# 09-USBUart_PPSMUX_UARTMUX.net
KiCad netlist of a schematic drawn in Altium Designer
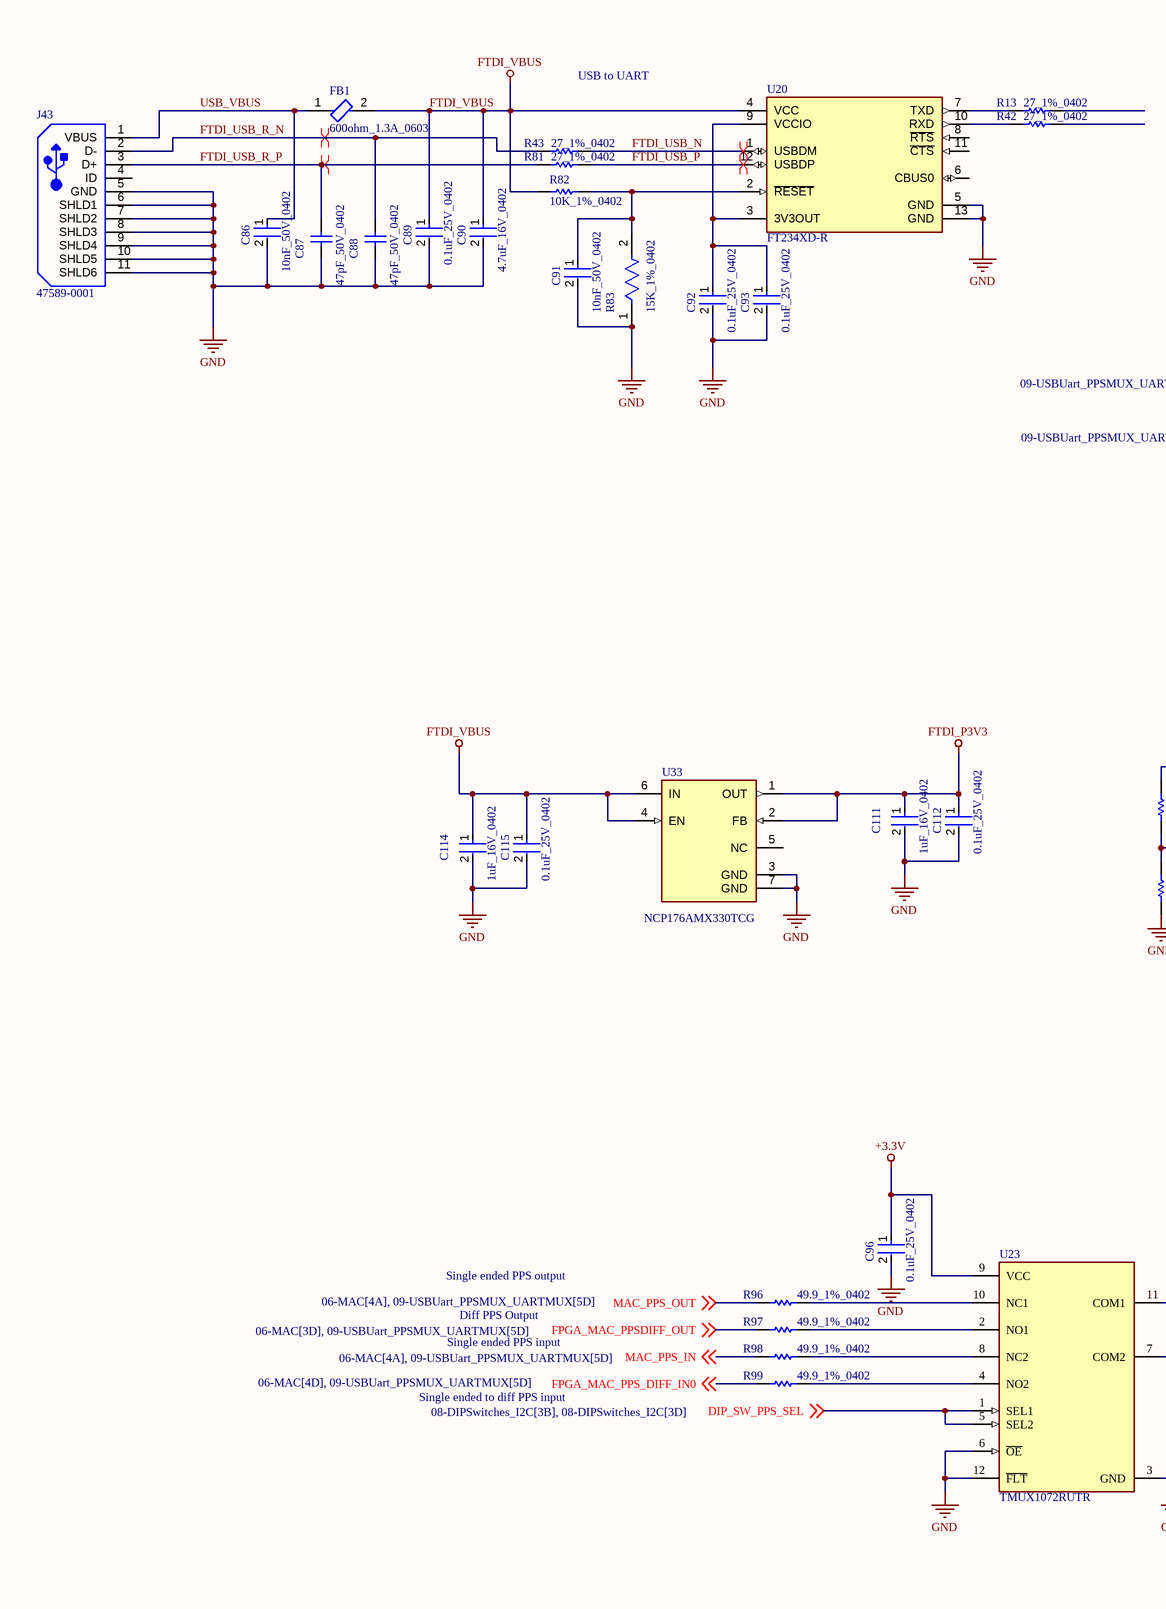
[diagram p0: 09-USBUart_PPSMUX_UARTMUX.SchDoc, left]
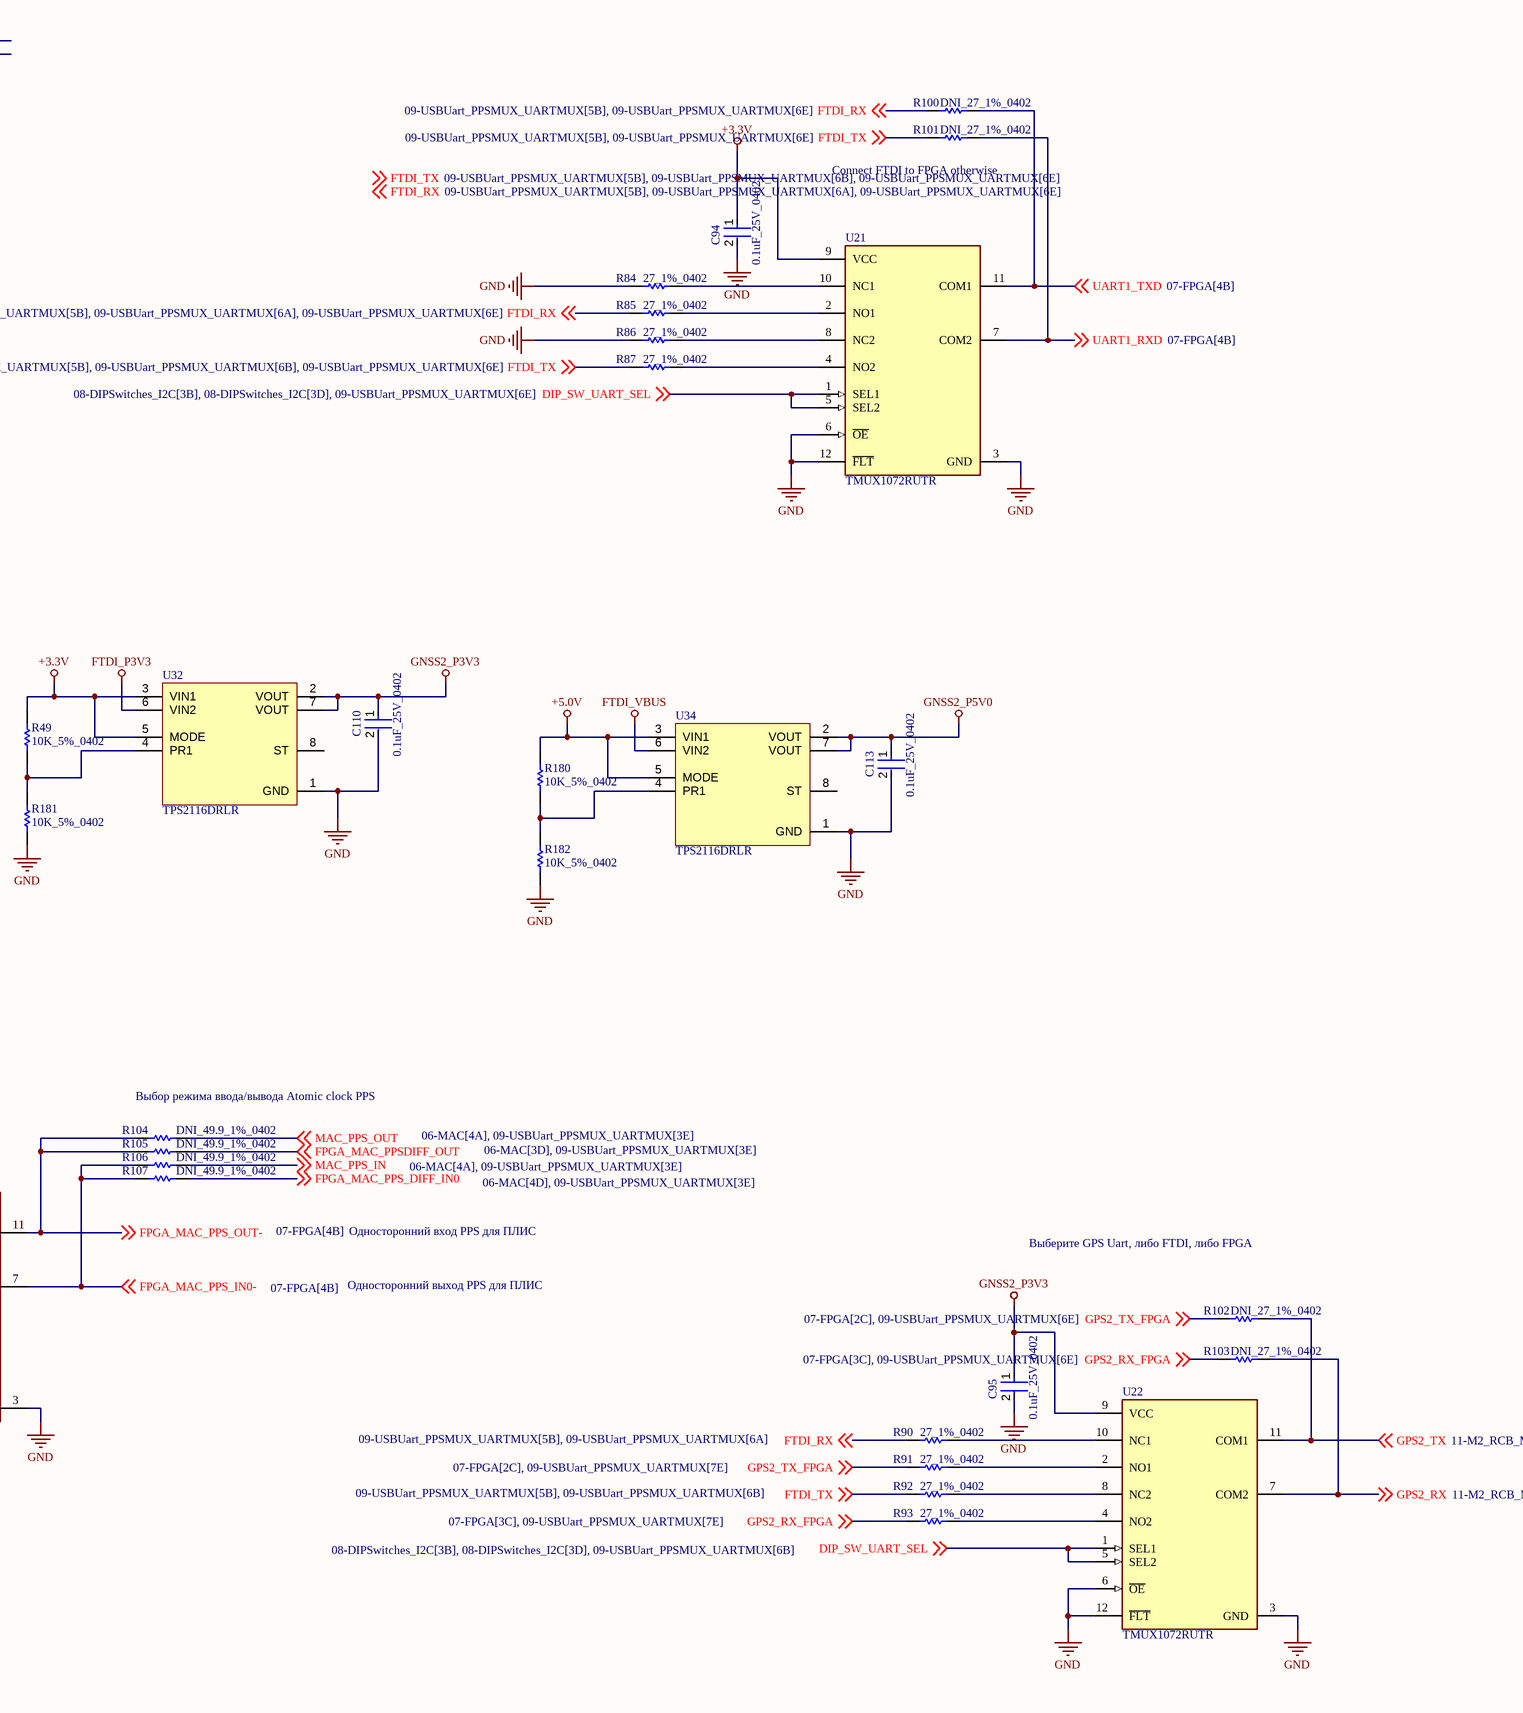
[diagram p1: 09-USBUart_PPSMUX_UARTMUX.SchDoc, right]

(export (version "E")
  (design (tool "Eeschema 10.0.6"))
  (components
    (comp (ref "C86")
      (value "10nF_50V_0402")
      (footprint "FP-CC0402-MFG")
      (description "CAP CER 10000PF 50V X7R 0402")
      (fields
        (field (name "OCTOPART") "https://octopart.com/cc0402krx7r9bb103-yageo-8376513")
        (field (name "MANUFACTURER PART NUMBER") "CC0402KRX7R9BB103")
      )
      (libsource (lib "Altium Content Vault") (part "11868f565c42a9108669ba33697ecf6"))
    )
    (comp (ref "C87")
      (value "47pF_50V_0402")
      (footprint "CAPC1005X55X25LL05T10")
      (fields (field (name "PART NUMBER") "GRM1555C1H470JA01D") (field (name "MANUFACTURER") "Murata"))
      (libsource (lib "Altium Content Vault") (part "CAP"))
    )
    (comp (ref "C88")
      (value "47pF_50V_0402")
      (footprint "CAPC1005X55X25LL05T10")
      (fields (field (name "PART NUMBER") "GRM1555C1H470JA01D") (field (name "MANUFACTURER") "Murata"))
      (libsource (lib "Altium Content Vault") (part "CAP"))
    )
    (comp (ref "C89")
      (value "0.1uF_25V_0402")
      (footprint "FP-0402-L_1_0_1-W_0_5_0_1-IPC_C")
      (description "General Purpose Ceramic Capacitor, 0402, 100nF, 10%, X7R, 15%, 25V")
      (fields (field (name "VOLTAGE") "25V") (field (name "TOLERANCE") "10%"))
      (libsource (lib "Altium Content Vault") (part "b4654b650e69147ec39a6b967a45e02"))
    )
    (comp (ref "C90")
      (value "4.7uF_16V_0402")
      (footprint "FP-CL829-IPC_C")
      (description "Cap Ceramic 4.7uF 16V X5R ±20% SMD 0402 +85°C Paper T/R")
      (fields (field (name "TOLERANCE") "20%"))
      (libsource (lib "Altium Content Vault") (part "b4654b650e69147ec39a6b967a45e02"))
    )
    (comp (ref "C91")
      (value "10nF_50V_0402")
      (footprint "FP-CC0402-MFG")
      (description "CAP CER 10000PF 50V X7R 0402")
      (fields
        (field (name "OCTOPART") "https://octopart.com/cc0402krx7r9bb103-yageo-8376513")
        (field (name "MANUFACTURER PART NUMBER") "CC0402KRX7R9BB103")
      )
      (libsource (lib "Altium Content Vault") (part "11868f565c42a9108669ba33697ecf6"))
    )
    (comp (ref "C92")
      (value "0.1uF_25V_0402")
      (footprint "FP-0402-L_1_0_1-W_0_5_0_1-IPC_C")
      (description "General Purpose Ceramic Capacitor, 0402, 100nF, 10%, X7R, 15%, 25V")
      (fields (field (name "VOLTAGE") "25V") (field (name "TOLERANCE") "10%"))
      (libsource (lib "Altium Content Vault") (part "b4654b650e69147ec39a6b967a45e02"))
    )
    (comp (ref "C93")
      (value "0.1uF_25V_0402")
      (footprint "FP-0402-L_1_0_1-W_0_5_0_1-IPC_C")
      (description "General Purpose Ceramic Capacitor, 0402, 100nF, 10%, X7R, 15%, 25V")
      (fields (field (name "VOLTAGE") "25V") (field (name "TOLERANCE") "10%"))
      (libsource (lib "Altium Content Vault") (part "b4654b650e69147ec39a6b967a45e02"))
    )
    (comp (ref "C94")
      (value "0.1uF_25V_0402")
      (footprint "FP-0402-L_1_0_1-W_0_5_0_1-IPC_C")
      (description "General Purpose Ceramic Capacitor, 0402, 100nF, 10%, X7R, 15%, 25V")
      (fields (field (name "VOLTAGE") "25V") (field (name "TOLERANCE") "10%"))
      (libsource (lib "Altium Content Vault") (part "b4654b650e69147ec39a6b967a45e02"))
    )
    (comp (ref "C95")
      (value "0.1uF_25V_0402")
      (footprint "FP-0402-L_1_0_1-W_0_5_0_1-IPC_C")
      (description "General Purpose Ceramic Capacitor, 0402, 100nF, 10%, X7R, 15%, 25V")
      (fields (field (name "VOLTAGE") "25V") (field (name "TOLERANCE") "10%"))
      (libsource (lib "Altium Content Vault") (part "b4654b650e69147ec39a6b967a45e02"))
    )
    (comp (ref "C96")
      (value "0.1uF_25V_0402")
      (footprint "FP-0402-L_1_0_1-W_0_5_0_1-IPC_C")
      (description "General Purpose Ceramic Capacitor, 0402, 100nF, 10%, X7R, 15%, 25V")
      (fields (field (name "VOLTAGE") "25V") (field (name "TOLERANCE") "10%"))
      (libsource (lib "Altium Content Vault") (part "b4654b650e69147ec39a6b967a45e02"))
    )
    (comp (ref "C110")
      (value "0.1uF_25V_0402")
      (footprint "FP-0402-L_1_0_1-W_0_5_0_1-IPC_C")
      (description "General Purpose Ceramic Capacitor, 0402, 100nF, 10%, X7R, 15%, 25V")
      (fields (field (name "VOLTAGE") "25V") (field (name "TOLERANCE") "10%"))
      (libsource (lib "Altium Content Vault") (part "b4654b650e69147ec39a6b967a45e02"))
    )
    (comp (ref "C111")
      (value "1uF_16V_0402")
      (footprint "FP-0402-L_1_0_0_05-W_0_5-IPC_A")
      (description "None")
      (fields (field (name "TOLERANCE") "10%"))
      (libsource (lib "Altium Content Vault") (part "b4654b650e69147ec39a6b967a45e02"))
    )
    (comp (ref "C112")
      (value "0.1uF_25V_0402")
      (footprint "FP-0402-L_1_0_1-W_0_5_0_1-IPC_C")
      (description "General Purpose Ceramic Capacitor, 0402, 100nF, 10%, X7R, 15%, 25V")
      (fields (field (name "VOLTAGE") "25V") (field (name "TOLERANCE") "10%"))
      (libsource (lib "Altium Content Vault") (part "b4654b650e69147ec39a6b967a45e02"))
    )
    (comp (ref "C113")
      (value "0.1uF_25V_0402")
      (footprint "FP-0402-L_1_0_1-W_0_5_0_1-IPC_C")
      (description "General Purpose Ceramic Capacitor, 0402, 100nF, 10%, X7R, 15%, 25V")
      (fields (field (name "VOLTAGE") "25V") (field (name "TOLERANCE") "10%"))
      (libsource (lib "Altium Content Vault") (part "b4654b650e69147ec39a6b967a45e02"))
    )
    (comp (ref "C114")
      (value "1uF_16V_0402")
      (footprint "FP-0402-L_1_0_0_05-W_0_5-IPC_A")
      (description "None")
      (fields (field (name "TOLERANCE") "10%"))
      (libsource (lib "Altium Content Vault") (part "b4654b650e69147ec39a6b967a45e02"))
    )
    (comp (ref "C115")
      (value "0.1uF_25V_0402")
      (footprint "FP-0402-L_1_0_1-W_0_5_0_1-IPC_C")
      (description "General Purpose Ceramic Capacitor, 0402, 100nF, 10%, X7R, 15%, 25V")
      (fields (field (name "VOLTAGE") "25V") (field (name "TOLERANCE") "10%"))
      (libsource (lib "Altium Content Vault") (part "b4654b650e69147ec39a6b967a45e02"))
    )
    (comp (ref "FB1")
      (value "600ohm_1.3A_0603")
      (footprint "FP-BLM18-0_15-t0_8-IPC_A")
      (description "Chip Ferrite Bead, 0603, 600Ω @ 100MHz, 0.15Ω, 25%, 1.3A")
      (fields (field (name "TOLERANCE") "25%"))
      (libsource (lib "Altium Content Vault") (part "5f30dd21d616792df468990f7003faa"))
    )
    (comp (ref "J43")
      (value "47589-0001")
      (footprint "MOLX-47589-0001_V")
      (description "Right Angle Female Type AB Micro USB Connector, 30 V, 1.8 A, -30 to 85 degC, RoHS, Tape and Reel")
      (fields (field (name "MANUFACTURER") "Molex"))
      (libsource (lib "Altium Content Vault") (part "USB-5-6SHLD"))
    )
    (comp (ref "R13")
      (value "27_1%_0402")
      (footprint "RESC1005X40X25NL05T05")
      (fields (field (name "PART NUMBER") "CRCW040227R0FKED") (field (name "MANUFACTURER") "Vishay Dale"))
      (libsource (lib "Altium Content Vault") (part "RES"))
    )
    (comp (ref "R42")
      (value "27_1%_0402")
      (footprint "RESC1005X40X25NL05T05")
      (fields (field (name "PART NUMBER") "CRCW040227R0FKED") (field (name "MANUFACTURER") "Vishay Dale"))
      (libsource (lib "Altium Content Vault") (part "RES"))
    )
    (comp (ref "R43")
      (value "27_1%_0402")
      (footprint "RESC1005X40X25NL05T05")
      (fields (field (name "PART NUMBER") "CRCW040227R0FKED") (field (name "MANUFACTURER") "Vishay Dale"))
      (libsource (lib "Altium Content Vault") (part "RES"))
    )
    (comp (ref "R49")
      (value "10K_5%_0402")
      (footprint "RESC1005X40X25ML05T05")
      (fields (field (name "PART NUMBER") "ERJ-2GEJ103X") (field (name "MANUFACTURER") "Panasonic"))
      (libsource (lib "Altium Content Vault") (part "RES"))
    )
    (comp (ref "R81")
      (value "27_1%_0402")
      (footprint "RESC1005X40X25NL05T05")
      (fields (field (name "PART NUMBER") "CRCW040227R0FKED") (field (name "MANUFACTURER") "Vishay Dale"))
      (libsource (lib "Altium Content Vault") (part "RES"))
    )
    (comp (ref "R82")
      (value "10K_1%_0402")
      (footprint "RESC1005X40X25LL05T10")
      (fields (field (name "PART NUMBER") "RC0402FR-0710KL") (field (name "MANUFACTURER") "Yageo / Phycomp"))
      (libsource (lib "Altium Content Vault") (part "RES"))
    )
    (comp (ref "R83")
      (value "15K_1%_0402")
      (footprint "FP-ERJ2R-MFG")
      (description "RES SMD 15K OHM 1% 1/10W 0402")
      (fields (field (name "TOLERANCE") "1%") (field (name "MANUFACTURER PART NUMBER") "ERJ-2RKF1502X"))
      (libsource (lib "Altium Content Vault") (part "1029c3af85768c4190bb7ad29bc67b5"))
    )
    (comp (ref "R84")
      (value "27_1%_0402")
      (footprint "RESC1005X40X25NL05T05")
      (fields (field (name "PART NUMBER") "CRCW040227R0FKED") (field (name "MANUFACTURER") "Vishay Dale"))
      (libsource (lib "Altium Content Vault") (part "RES"))
    )
    (comp (ref "R85")
      (value "27_1%_0402")
      (footprint "RESC1005X40X25NL05T05")
      (fields (field (name "PART NUMBER") "CRCW040227R0FKED") (field (name "MANUFACTURER") "Vishay Dale"))
      (libsource (lib "Altium Content Vault") (part "RES"))
    )
    (comp (ref "R86")
      (value "27_1%_0402")
      (footprint "RESC1005X40X25NL05T05")
      (fields (field (name "PART NUMBER") "CRCW040227R0FKED") (field (name "MANUFACTURER") "Vishay Dale"))
      (libsource (lib "Altium Content Vault") (part "RES"))
    )
    (comp (ref "R87")
      (value "27_1%_0402")
      (footprint "RESC1005X40X25NL05T05")
      (fields (field (name "PART NUMBER") "CRCW040227R0FKED") (field (name "MANUFACTURER") "Vishay Dale"))
      (libsource (lib "Altium Content Vault") (part "RES"))
    )
    (comp (ref "R90")
      (value "27_1%_0402")
      (footprint "RESC1005X40X25NL05T05")
      (fields (field (name "PART NUMBER") "CRCW040227R0FKED") (field (name "MANUFACTURER") "Vishay Dale"))
      (libsource (lib "Altium Content Vault") (part "RES"))
    )
    (comp (ref "R91")
      (value "27_1%_0402")
      (footprint "RESC1005X40X25NL05T05")
      (fields (field (name "PART NUMBER") "CRCW040227R0FKED") (field (name "MANUFACTURER") "Vishay Dale"))
      (libsource (lib "Altium Content Vault") (part "RES"))
    )
    (comp (ref "R92")
      (value "27_1%_0402")
      (footprint "RESC1005X40X25NL05T05")
      (fields (field (name "PART NUMBER") "CRCW040227R0FKED") (field (name "MANUFACTURER") "Vishay Dale"))
      (libsource (lib "Altium Content Vault") (part "RES"))
    )
    (comp (ref "R93")
      (value "27_1%_0402")
      (footprint "RESC1005X40X25NL05T05")
      (fields (field (name "PART NUMBER") "CRCW040227R0FKED") (field (name "MANUFACTURER") "Vishay Dale"))
      (libsource (lib "Altium Content Vault") (part "RES"))
    )
    (comp (ref "R96")
      (value "49.9_1%_0402")
      (footprint "RESC1005X40X25LL05T10")
      (fields (field (name "MANUFACTURER") "Yageo / Phycomp") (field (name "PART NUMBER") "RC0402FR-0749R9L"))
      (libsource (lib "Altium Content Vault") (part "RES"))
    )
    (comp (ref "R97")
      (value "49.9_1%_0402")
      (footprint "RESC1005X40X25LL05T10")
      (fields (field (name "MANUFACTURER") "Yageo / Phycomp") (field (name "PART NUMBER") "RC0402FR-0749R9L"))
      (libsource (lib "Altium Content Vault") (part "RES"))
    )
    (comp (ref "R98")
      (value "49.9_1%_0402")
      (footprint "RESC1005X40X25LL05T10")
      (fields (field (name "MANUFACTURER") "Yageo / Phycomp") (field (name "PART NUMBER") "RC0402FR-0749R9L"))
      (libsource (lib "Altium Content Vault") (part "RES"))
    )
    (comp (ref "R99")
      (value "49.9_1%_0402")
      (footprint "RESC1005X40X25LL05T10")
      (fields (field (name "MANUFACTURER") "Yageo / Phycomp") (field (name "PART NUMBER") "RC0402FR-0749R9L"))
      (libsource (lib "Altium Content Vault") (part "RES"))
    )
    (comp (ref "R100")
      (value "DNI_27_1%_0402")
      (footprint "RESC1005X40X25NL05T05")
      (fields (field (name "PART NUMBER") "CRCW040227R0FKED") (field (name "MANUFACTURER") "Vishay Dale"))
      (libsource (lib "Altium Content Vault") (part "RES"))
    )
    (comp (ref "R101")
      (value "DNI_27_1%_0402")
      (footprint "RESC1005X40X25NL05T05")
      (fields (field (name "PART NUMBER") "CRCW040227R0FKED") (field (name "MANUFACTURER") "Vishay Dale"))
      (libsource (lib "Altium Content Vault") (part "RES"))
    )
    (comp (ref "R102")
      (value "DNI_27_1%_0402")
      (footprint "RESC1005X40X25NL05T05")
      (fields (field (name "PART NUMBER") "CRCW040227R0FKED") (field (name "MANUFACTURER") "Vishay Dale"))
      (libsource (lib "Altium Content Vault") (part "RES"))
    )
    (comp (ref "R103")
      (value "DNI_27_1%_0402")
      (footprint "RESC1005X40X25NL05T05")
      (fields (field (name "PART NUMBER") "CRCW040227R0FKED") (field (name "MANUFACTURER") "Vishay Dale"))
      (libsource (lib "Altium Content Vault") (part "RES"))
    )
    (comp (ref "R104")
      (value "DNI_49.9_1%_0402")
      (footprint "RESC1005X40X25LL05T10")
      (fields (field (name "MANUFACTURER") "Yageo / Phycomp") (field (name "PART NUMBER") "RC0402FR-0749R9L"))
      (libsource (lib "Altium Content Vault") (part "RES"))
    )
    (comp (ref "R105")
      (value "DNI_49.9_1%_0402")
      (footprint "RESC1005X40X25LL05T10")
      (fields (field (name "MANUFACTURER") "Yageo / Phycomp") (field (name "PART NUMBER") "RC0402FR-0749R9L"))
      (libsource (lib "Altium Content Vault") (part "RES"))
    )
    (comp (ref "R106")
      (value "DNI_49.9_1%_0402")
      (footprint "RESC1005X40X25LL05T10")
      (fields (field (name "MANUFACTURER") "Yageo / Phycomp") (field (name "PART NUMBER") "RC0402FR-0749R9L"))
      (libsource (lib "Altium Content Vault") (part "RES"))
    )
    (comp (ref "R107")
      (value "DNI_49.9_1%_0402")
      (footprint "RESC1005X40X25LL05T10")
      (fields (field (name "MANUFACTURER") "Yageo / Phycomp") (field (name "PART NUMBER") "RC0402FR-0749R9L"))
      (libsource (lib "Altium Content Vault") (part "RES"))
    )
    (comp (ref "R180")
      (value "10K_5%_0402")
      (footprint "RESC1005X40X25ML05T05")
      (fields (field (name "PART NUMBER") "ERJ-2GEJ103X") (field (name "MANUFACTURER") "Panasonic"))
      (libsource (lib "Altium Content Vault") (part "RES"))
    )
    (comp (ref "R181")
      (value "10K_5%_0402")
      (footprint "RESC1005X40X25ML05T05")
      (fields (field (name "PART NUMBER") "ERJ-2GEJ103X") (field (name "MANUFACTURER") "Panasonic"))
      (libsource (lib "Altium Content Vault") (part "RES"))
    )
    (comp (ref "R182")
      (value "10K_5%_0402")
      (footprint "RESC1005X40X25ML05T05")
      (fields (field (name "PART NUMBER") "ERJ-2GEJ103X") (field (name "MANUFACTURER") "Panasonic"))
      (libsource (lib "Altium Content Vault") (part "RES"))
    )
    (comp (ref "U20")
      (value "FT234XD-R")
      (footprint "FP-DFN-12-IPC_B")
      (description "IC USB SERIAL BASIC UART 12DFN")
      (libsource (lib "Altium Content Vault") (part "4bef3367ed9f9051bcb84ab46edda1c"))
    )
    (comp (ref "U21")
      (value "TMUX1072RUTR")
      (footprint "FP-RUT0012A-MFG")
      (description "IC SWITCH SPDT DUAL 12UQFN")
      (libsource (lib "Altium Content Vault") (part "12a319ab100cd6cfe745e35972674f5"))
    )
    (comp (ref "U22")
      (value "TMUX1072RUTR")
      (footprint "FP-RUT0012A-MFG")
      (description "IC SWITCH SPDT DUAL 12UQFN")
      (libsource (lib "Altium Content Vault") (part "12a319ab100cd6cfe745e35972674f5"))
    )
    (comp (ref "U23")
      (value "TMUX1072RUTR")
      (footprint "FP-RUT0012A-MFG")
      (description "IC SWITCH SPDT DUAL 12UQFN")
      (libsource (lib "Altium Content Vault") (part "12a319ab100cd6cfe745e35972674f5"))
    )
    (comp (ref "U32")
      (value "TPS2116DRLR")
      (footprint "IC_TPS2116")
      (description "1.6-V to 5.5-V, 40-mΩ, 2.5-A, low-IQ, priority power multiplexer 8-SOT-5X3 -40 to 125")
      (fields (field (name "MF") "Texas Instruments"))
      (libsource (lib "LotusSound") (part "IC_TPS2116DRLR"))
    )
    (comp (ref "U33")
      (value "NCP176AMX330TCG")
      (footprint "FP-711AT-MFG")
      (description "IC REG LINEAR 3.3V 500MA 6XDFN")
      (fields
        (field (name "MANUFACTURER") "ON Semiconductor")
        (field (name "OCTOPART") "https://octopart.com/ncp176amx330tcg-on+semiconductor-61522616")
      )
      (libsource (lib "Altium Content Vault") (part "a38d0f79c2a9f01c07a7e52882ed186"))
    )
    (comp (ref "U34")
      (value "TPS2116DRLR")
      (footprint "IC_TPS2116")
      (description "1.6-V to 5.5-V, 40-mΩ, 2.5-A, low-IQ, priority power multiplexer 8-SOT-5X3 -40 to 125")
      (fields (field (name "MF") "Texas Instruments"))
      (libsource (lib "LotusSound") (part "IC_TPS2116DRLR"))
    )
  )
  (nets
    (net (code "1") (name "+3.3V") (class "Default")
      (node (ref "C94") (pin "1") (pinfunction "1_1") (pintype "passive"))
      (node (ref "C96") (pin "1") (pinfunction "1_1") (pintype "passive"))
      (node (ref "R49") (pin "2") (pinfunction "2_2") (pintype "passive"))
      (node (ref "U21") (pin "9") (pinfunction "VCC_9") (pintype "power_in"))
      (node (ref "U23") (pin "9") (pinfunction "VCC_9") (pintype "power_in"))
      (node (ref "U32") (pin "3") (pinfunction "VIN1_3") (pintype "passive"))
      (node (ref "U32") (pin "5") (pinfunction "MODE_5") (pintype "passive"))
    )
    (net (code "2") (name "+5.0V") (class "Default")
      (node (ref "R180") (pin "2") (pinfunction "2_2") (pintype "passive"))
      (node (ref "U34") (pin "3") (pinfunction "VIN1_3") (pintype "passive"))
      (node (ref "U34") (pin "5") (pinfunction "MODE_5") (pintype "passive"))
    )
    (net (code "3") (name "/FTDI_USB_N") (class "Default")
      (node (ref "R43") (pin "2") (pinfunction "2_2") (pintype "passive"))
      (node (ref "U20") (pin "1") (pinfunction "USBDM_1") (pintype "bidirectional"))
    )
    (net (code "4") (name "/FTDI_USB_P") (class "Default")
      (node (ref "R81") (pin "2") (pinfunction "2_2") (pintype "passive"))
      (node (ref "U20") (pin "12") (pinfunction "USBDP_12") (pintype "bidirectional"))
    )
    (net (code "5") (name "/FTDI_USB_R_N") (class "Default")
      (node (ref "C88") (pin "2") (pinfunction "2_2") (pintype "passive"))
      (node (ref "J43") (pin "2") (pinfunction "D-_2") (pintype "passive"))
      (node (ref "R43") (pin "1") (pinfunction "1_1") (pintype "passive"))
    )
    (net (code "6") (name "/FTDI_USB_R_P") (class "Default")
      (node (ref "C87") (pin "2") (pinfunction "2_2") (pintype "passive"))
      (node (ref "J43") (pin "3") (pinfunction "D+_3") (pintype "passive"))
      (node (ref "R81") (pin "1") (pinfunction "1_1") (pintype "passive"))
    )
    (net (code "7") (name "/USB_VBUS") (class "Default")
      (node (ref "C86") (pin "1") (pinfunction "1_1") (pintype "passive"))
      (node (ref "FB1") (pin "1") (pinfunction "1_1") (pintype "passive"))
      (node (ref "J43") (pin "1") (pinfunction "VBUS_1") (pintype "passive"))
    )
    (net (code "8") (name "DIP_SW_PPS_SEL") (class "Default")
      (node (ref "U23") (pin "1") (pinfunction "SEL1_1") (pintype "input"))
      (node (ref "U23") (pin "5") (pinfunction "SEL2_5") (pintype "input"))
    )
    (net (code "9") (name "DIP_SW_UART_SEL") (class "Default")
      (node (ref "U21") (pin "1") (pinfunction "SEL1_1") (pintype "input"))
      (node (ref "U21") (pin "5") (pinfunction "SEL2_5") (pintype "input"))
      (node (ref "U22") (pin "1") (pinfunction "SEL1_1") (pintype "input"))
      (node (ref "U22") (pin "5") (pinfunction "SEL2_5") (pintype "input"))
    )
    (net (code "10") (name "FPGA_MAC_PPSDIFF_OUT") (class "Default")
      (node (ref "R105") (pin "2") (pinfunction "2_2") (pintype "passive"))
      (node (ref "R97") (pin "1") (pinfunction "1_1") (pintype "passive"))
    )
    (net (code "11") (name "FPGA_MAC_PPS_DIFF_IN0") (class "Default")
      (node (ref "R107") (pin "2") (pinfunction "2_2") (pintype "passive"))
      (node (ref "R99") (pin "1") (pinfunction "1_1") (pintype "passive"))
    )
    (net (code "12") (name "FPGA_MAC_PPS_IN0-") (class "Default")
      (node (ref "R106") (pin "1") (pinfunction "1_1") (pintype "passive"))
      (node (ref "R107") (pin "1") (pinfunction "1_1") (pintype "passive"))
      (node (ref "U23") (pin "7") (pinfunction "COM2_7") (pintype "passive"))
    )
    (net (code "13") (name "FPGA_MAC_PPS_OUT-") (class "Default")
      (node (ref "R104") (pin "1") (pinfunction "1_1") (pintype "passive"))
      (node (ref "R105") (pin "1") (pinfunction "1_1") (pintype "passive"))
      (node (ref "U23") (pin "11") (pinfunction "COM1_11") (pintype "passive"))
    )
    (net (code "14") (name "FTDI_P3V3") (class "Default")
      (node (ref "C111") (pin "1") (pinfunction "1_1") (pintype "passive"))
      (node (ref "C112") (pin "1") (pinfunction "1_1") (pintype "passive"))
      (node (ref "U32") (pin "6") (pinfunction "VIN2_6") (pintype "passive"))
      (node (ref "U33") (pin "1") (pinfunction "OUT_1") (pintype "output"))
      (node (ref "U33") (pin "2") (pinfunction "FB_2") (pintype "input"))
    )
    (net (code "15") (name "FTDI_RX") (class "Default")
      (node (ref "R100") (pin "1") (pinfunction "1_1") (pintype "passive"))
      (node (ref "R85") (pin "1") (pinfunction "1_1") (pintype "passive"))
      (node (ref "R90") (pin "1") (pinfunction "1_1") (pintype "passive"))
    )
    (net (code "16") (name "FTDI_TX") (class "Default")
      (node (ref "R101") (pin "1") (pinfunction "1_1") (pintype "passive"))
      (node (ref "R87") (pin "1") (pinfunction "1_1") (pintype "passive"))
      (node (ref "R92") (pin "1") (pinfunction "1_1") (pintype "passive"))
    )
    (net (code "17") (name "FTDI_VBUS") (class "Default")
      (node (ref "C114") (pin "1") (pinfunction "1_1") (pintype "passive"))
      (node (ref "C115") (pin "1") (pinfunction "1_1") (pintype "passive"))
      (node (ref "C89") (pin "1") (pinfunction "1_1") (pintype "passive"))
      (node (ref "C90") (pin "1") (pinfunction "1_1") (pintype "passive"))
      (node (ref "FB1") (pin "2") (pinfunction "2_2") (pintype "passive"))
      (node (ref "R82") (pin "2") (pinfunction "2_2") (pintype "passive"))
      (node (ref "U20") (pin "4") (pinfunction "VCC_4") (pintype "power_in"))
      (node (ref "U33") (pin "4") (pinfunction "EN_4") (pintype "input"))
      (node (ref "U33") (pin "6") (pinfunction "IN_6") (pintype "power_in"))
      (node (ref "U34") (pin "6") (pinfunction "VIN2_6") (pintype "passive"))
    )
    (net (code "18") (name "GND") (class "Default")
      (node (ref "C110") (pin "2") (pinfunction "2_2") (pintype "passive"))
      (node (ref "C111") (pin "2") (pinfunction "2_2") (pintype "passive"))
      (node (ref "C112") (pin "2") (pinfunction "2_2") (pintype "passive"))
      (node (ref "C113") (pin "2") (pinfunction "2_2") (pintype "passive"))
      (node (ref "C114") (pin "2") (pinfunction "2_2") (pintype "passive"))
      (node (ref "C115") (pin "2") (pinfunction "2_2") (pintype "passive"))
      (node (ref "C86") (pin "2") (pinfunction "2_2") (pintype "passive"))
      (node (ref "C87") (pin "1") (pinfunction "1_1") (pintype "passive"))
      (node (ref "C88") (pin "1") (pinfunction "1_1") (pintype "passive"))
      (node (ref "C89") (pin "2") (pinfunction "2_2") (pintype "passive"))
      (node (ref "C90") (pin "2") (pinfunction "2_2") (pintype "passive"))
      (node (ref "C91") (pin "2") (pinfunction "2_2") (pintype "passive"))
      (node (ref "C92") (pin "2") (pinfunction "2_2") (pintype "passive"))
      (node (ref "C93") (pin "2") (pinfunction "2_2") (pintype "passive"))
      (node (ref "C94") (pin "2") (pinfunction "2_2") (pintype "passive"))
      (node (ref "C95") (pin "2") (pinfunction "2_2") (pintype "passive"))
      (node (ref "C96") (pin "2") (pinfunction "2_2") (pintype "passive"))
      (node (ref "J43") (pin "10") (pinfunction "SHLD5_10") (pintype "passive"))
      (node (ref "J43") (pin "11") (pinfunction "SHLD6_11") (pintype "passive"))
      (node (ref "J43") (pin "5") (pinfunction "GND_5") (pintype "passive"))
      (node (ref "J43") (pin "6") (pinfunction "SHLD1_6") (pintype "passive"))
      (node (ref "J43") (pin "7") (pinfunction "SHLD2_7") (pintype "passive"))
      (node (ref "J43") (pin "8") (pinfunction "SHLD3_8") (pintype "passive"))
      (node (ref "J43") (pin "9") (pinfunction "SHLD4_9") (pintype "passive"))
      (node (ref "R181") (pin "1") (pinfunction "1_1") (pintype "passive"))
      (node (ref "R182") (pin "1") (pinfunction "1_1") (pintype "passive"))
      (node (ref "R83") (pin "1") (pinfunction "1_1") (pintype "passive"))
      (node (ref "R84") (pin "1") (pinfunction "1_1") (pintype "passive"))
      (node (ref "R86") (pin "1") (pinfunction "1_1") (pintype "passive"))
      (node (ref "U20") (pin "13") (pinfunction "GND_13") (pintype "power_in"))
      (node (ref "U20") (pin "5") (pinfunction "GND_5") (pintype "power_in"))
      (node (ref "U21") (pin "12") (pinfunction "~{FLT}_12") (pintype "open_collector"))
      (node (ref "U21") (pin "3") (pinfunction "GND_3") (pintype "power_in"))
      (node (ref "U21") (pin "6") (pinfunction "~{OE}_6") (pintype "input"))
      (node (ref "U22") (pin "12") (pinfunction "~{FLT}_12") (pintype "open_collector"))
      (node (ref "U22") (pin "3") (pinfunction "GND_3") (pintype "power_in"))
      (node (ref "U22") (pin "6") (pinfunction "~{OE}_6") (pintype "input"))
      (node (ref "U23") (pin "12") (pinfunction "~{FLT}_12") (pintype "open_collector"))
      (node (ref "U23") (pin "3") (pinfunction "GND_3") (pintype "power_in"))
      (node (ref "U23") (pin "6") (pinfunction "~{OE}_6") (pintype "input"))
      (node (ref "U32") (pin "1") (pinfunction "GND_1") (pintype "passive"))
      (node (ref "U33") (pin "3") (pinfunction "GND_3") (pintype "power_in"))
      (node (ref "U33") (pin "7") (pinfunction "GND_7") (pintype "power_in"))
      (node (ref "U34") (pin "1") (pinfunction "GND_1") (pintype "passive"))
    )
    (net (code "19") (name "GNSS2_P3V3") (class "Default")
      (node (ref "C110") (pin "1") (pinfunction "1_1") (pintype "passive"))
      (node (ref "C95") (pin "1") (pinfunction "1_1") (pintype "passive"))
      (node (ref "U22") (pin "9") (pinfunction "VCC_9") (pintype "power_in"))
      (node (ref "U32") (pin "2") (pinfunction "VOUT_2") (pintype "passive"))
      (node (ref "U32") (pin "7") (pinfunction "VOUT_7") (pintype "passive"))
    )
    (net (code "20") (name "GNSS2_P5V0") (class "Default")
      (node (ref "C113") (pin "1") (pinfunction "1_1") (pintype "passive"))
      (node (ref "U34") (pin "2") (pinfunction "VOUT_2") (pintype "passive"))
      (node (ref "U34") (pin "7") (pinfunction "VOUT_7") (pintype "passive"))
    )
    (net (code "21") (name "GPS2_RX") (class "Default")
      (node (ref "R103") (pin "2") (pinfunction "2_2") (pintype "passive"))
      (node (ref "U22") (pin "7") (pinfunction "COM2_7") (pintype "passive"))
    )
    (net (code "22") (name "GPS2_RX_FPGA") (class "Default")
      (node (ref "R103") (pin "1") (pinfunction "1_1") (pintype "passive"))
      (node (ref "R93") (pin "1") (pinfunction "1_1") (pintype "passive"))
    )
    (net (code "23") (name "GPS2_TX") (class "Default")
      (node (ref "R102") (pin "2") (pinfunction "2_2") (pintype "passive"))
      (node (ref "U22") (pin "11") (pinfunction "COM1_11") (pintype "passive"))
    )
    (net (code "24") (name "GPS2_TX_FPGA") (class "Default")
      (node (ref "R102") (pin "1") (pinfunction "1_1") (pintype "passive"))
      (node (ref "R91") (pin "1") (pinfunction "1_1") (pintype "passive"))
    )
    (net (code "25") (name "MAC_PPS_IN") (class "Default")
      (node (ref "R106") (pin "2") (pinfunction "2_2") (pintype "passive"))
      (node (ref "R98") (pin "1") (pinfunction "1_1") (pintype "passive"))
    )
    (net (code "26") (name "MAC_PPS_OUT") (class "Default")
      (node (ref "R104") (pin "2") (pinfunction "2_2") (pintype "passive"))
      (node (ref "R96") (pin "1") (pinfunction "1_1") (pintype "passive"))
    )
    (net (code "27") (name "Net-(U20-3V3OUT)") (class "Default")
      (node (ref "C92") (pin "1") (pinfunction "1_1") (pintype "passive"))
      (node (ref "C93") (pin "1") (pinfunction "1_1") (pintype "passive"))
      (node (ref "U20") (pin "3") (pinfunction "3V3OUT_3") (pintype "power_in"))
      (node (ref "U20") (pin "9") (pinfunction "VCCIO_9") (pintype "power_in"))
    )
    (net (code "28") (name "Net-(U20-RXD)") (class "Default")
      (node (ref "R42") (pin "1") (pinfunction "1_1") (pintype "passive"))
      (node (ref "U20") (pin "10") (pinfunction "RXD_10") (pintype "output"))
    )
    (net (code "29") (name "Net-(U20-TXD)") (class "Default")
      (node (ref "R13") (pin "1") (pinfunction "1_1") (pintype "passive"))
      (node (ref "U20") (pin "7") (pinfunction "TXD_7") (pintype "output"))
    )
    (net (code "30") (name "Net-(U20-~{RESET})") (class "Default")
      (node (ref "C91") (pin "1") (pinfunction "1_1") (pintype "passive"))
      (node (ref "R82") (pin "1") (pinfunction "1_1") (pintype "passive"))
      (node (ref "R83") (pin "2") (pinfunction "2_2") (pintype "passive"))
      (node (ref "U20") (pin "2") (pinfunction "~{RESET}_2") (pintype "input"))
    )
    (net (code "31") (name "Net-(U21-NC1)") (class "Default")
      (node (ref "R84") (pin "2") (pinfunction "2_2") (pintype "passive"))
      (node (ref "U21") (pin "10") (pinfunction "NC1_10") (pintype "passive"))
    )
    (net (code "32") (name "Net-(U21-NC2)") (class "Default")
      (node (ref "R86") (pin "2") (pinfunction "2_2") (pintype "passive"))
      (node (ref "U21") (pin "8") (pinfunction "NC2_8") (pintype "passive"))
    )
    (net (code "33") (name "Net-(U21-NO1)") (class "Default")
      (node (ref "R85") (pin "2") (pinfunction "2_2") (pintype "passive"))
      (node (ref "U21") (pin "2") (pinfunction "NO1_2") (pintype "passive"))
    )
    (net (code "34") (name "Net-(U21-NO2)") (class "Default")
      (node (ref "R87") (pin "2") (pinfunction "2_2") (pintype "passive"))
      (node (ref "U21") (pin "4") (pinfunction "NO2_4") (pintype "passive"))
    )
    (net (code "35") (name "Net-(U22-NC1)") (class "Default")
      (node (ref "R90") (pin "2") (pinfunction "2_2") (pintype "passive"))
      (node (ref "U22") (pin "10") (pinfunction "NC1_10") (pintype "passive"))
    )
    (net (code "36") (name "Net-(U22-NC2)") (class "Default")
      (node (ref "R92") (pin "2") (pinfunction "2_2") (pintype "passive"))
      (node (ref "U22") (pin "8") (pinfunction "NC2_8") (pintype "passive"))
    )
    (net (code "37") (name "Net-(U22-NO1)") (class "Default")
      (node (ref "R91") (pin "2") (pinfunction "2_2") (pintype "passive"))
      (node (ref "U22") (pin "2") (pinfunction "NO1_2") (pintype "passive"))
    )
    (net (code "38") (name "Net-(U22-NO2)") (class "Default")
      (node (ref "R93") (pin "2") (pinfunction "2_2") (pintype "passive"))
      (node (ref "U22") (pin "4") (pinfunction "NO2_4") (pintype "passive"))
    )
    (net (code "39") (name "Net-(U23-NC1)") (class "Default")
      (node (ref "R96") (pin "2") (pinfunction "2_2") (pintype "passive"))
      (node (ref "U23") (pin "10") (pinfunction "NC1_10") (pintype "passive"))
    )
    (net (code "40") (name "Net-(U23-NC2)") (class "Default")
      (node (ref "R98") (pin "2") (pinfunction "2_2") (pintype "passive"))
      (node (ref "U23") (pin "8") (pinfunction "NC2_8") (pintype "passive"))
    )
    (net (code "41") (name "Net-(U23-NO1)") (class "Default")
      (node (ref "R97") (pin "2") (pinfunction "2_2") (pintype "passive"))
      (node (ref "U23") (pin "2") (pinfunction "NO1_2") (pintype "passive"))
    )
    (net (code "42") (name "Net-(U23-NO2)") (class "Default")
      (node (ref "R99") (pin "2") (pinfunction "2_2") (pintype "passive"))
      (node (ref "U23") (pin "4") (pinfunction "NO2_4") (pintype "passive"))
    )
    (net (code "43") (name "Net-(U32-PR1)") (class "Default")
      (node (ref "R181") (pin "2") (pinfunction "2_2") (pintype "passive"))
      (node (ref "R49") (pin "1") (pinfunction "1_1") (pintype "passive"))
      (node (ref "U32") (pin "4") (pinfunction "PR1_4") (pintype "passive"))
    )
    (net (code "44") (name "Net-(U34-PR1)") (class "Default")
      (node (ref "R180") (pin "1") (pinfunction "1_1") (pintype "passive"))
      (node (ref "R182") (pin "2") (pinfunction "2_2") (pintype "passive"))
      (node (ref "U34") (pin "4") (pinfunction "PR1_4") (pintype "passive"))
    )
    (net (code "45") (name "UART1_RXD") (class "Default")
      (node (ref "R101") (pin "2") (pinfunction "2_2") (pintype "passive"))
      (node (ref "U21") (pin "7") (pinfunction "COM2_7") (pintype "passive"))
    )
    (net (code "46") (name "UART1_TXD") (class "Default")
      (node (ref "R100") (pin "2") (pinfunction "2_2") (pintype "passive"))
      (node (ref "U21") (pin "11") (pinfunction "COM1_11") (pintype "passive"))
    )
    (net (code "47") (name "unconnected-(J43-ID-Pad4)") (class "Default")
      (node (ref "J43") (pin "4") (pinfunction "ID_4") (pintype "passive"))
    )
    (net (code "48") (name "unconnected-(R13-Pad2)") (class "Default")
      (node (ref "R13") (pin "2") (pinfunction "2_2") (pintype "passive"))
    )
    (net (code "49") (name "unconnected-(R42-Pad2)") (class "Default")
      (node (ref "R42") (pin "2") (pinfunction "2_2") (pintype "passive"))
    )
    (net (code "50") (name "unconnected-(U20-CBUS0-Pad6)") (class "Default")
      (node (ref "U20") (pin "6") (pinfunction "CBUS0_6") (pintype "bidirectional"))
    )
    (net (code "51") (name "unconnected-(U20-~{CTS}-Pad11)") (class "Default")
      (node (ref "U20") (pin "11") (pinfunction "~{CTS}_11") (pintype "input"))
    )
    (net (code "52") (name "unconnected-(U20-~{RTS}-Pad8)") (class "Default")
      (node (ref "U20") (pin "8") (pinfunction "~{RTS}_8") (pintype "input"))
    )
    (net (code "53") (name "unconnected-(U32-ST-Pad8)") (class "Default")
      (node (ref "U32") (pin "8") (pinfunction "ST_8") (pintype "passive"))
    )
    (net (code "54") (name "unconnected-(U33-NC-Pad5)") (class "Default")
      (node (ref "U33") (pin "5") (pinfunction "NC_5") (pintype "passive"))
    )
    (net (code "55") (name "unconnected-(U34-ST-Pad8)") (class "Default")
      (node (ref "U34") (pin "8") (pinfunction "ST_8") (pintype "passive"))
    )
  )
)
